# primero.net
KiCad netlist of a schematic drawn in EAGLE
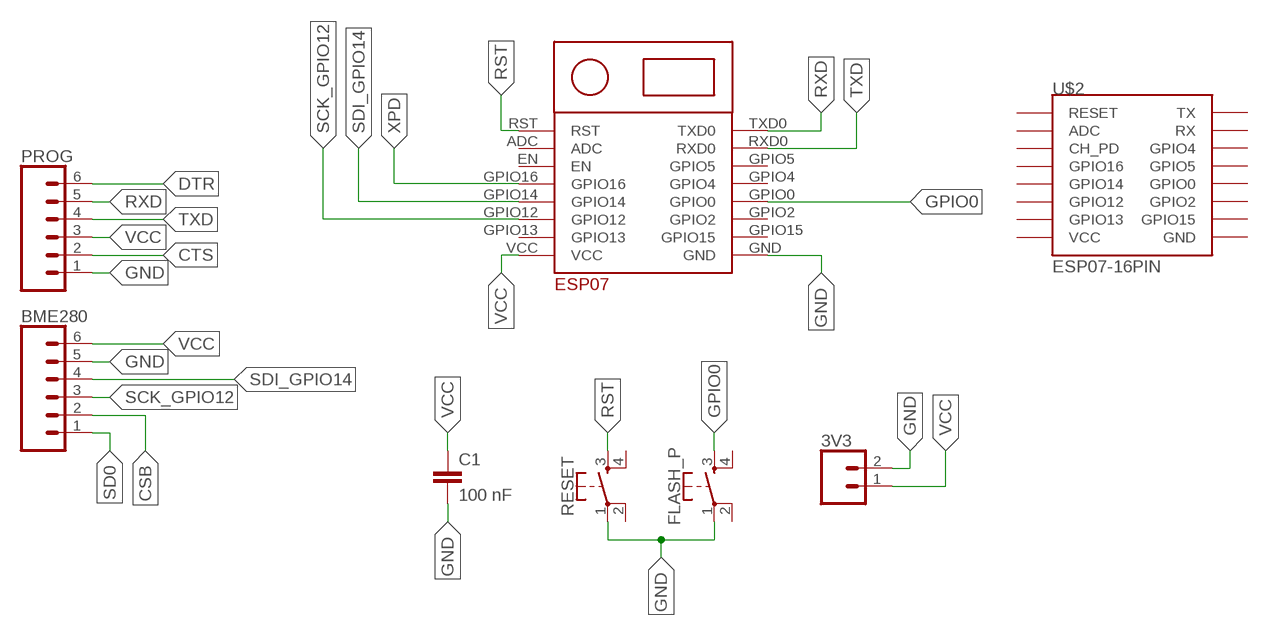
[diagram p0: schematic, sheet 1]

(export (version "E")
  (design (tool "Eeschema 10.0.6"))
  (components
    (comp (ref "3V3")
      (value "CONN_02JST-PTH-2")
      (footprint "eagle-import:JST-2-PTH")
      (libsource (lib "eagle-import") (part "CONN_02JST-PTH-2"))
    )
    (comp (ref "BME280")
      (value "CONN_06SILK_FEMALE_PTH")
      (footprint "eagle-import:1X06")
      (libsource (lib "eagle-import") (part "CONN_06SILK_FEMALE_PTH"))
    )
    (comp (ref "C1")
      (value "100 nF")
      (footprint "eagle-import:C0805")
      (libsource (lib "eagle-import") (part "C-EUC0805"))
    )
    (comp (ref "FLASH_P")
      (value "MOMENTARY-SWITCH-SPST-2-SMD-4.6X2.8MM")
      (footprint "eagle-import:TACTILE_SWITCH_SMD_4.6X2.8MM")
      (libsource (lib "eagle-import") (part "MOMENTARY-SWITCH-SPST-2-SMD-4.6X2.8MM"))
    )
    (comp (ref "PROG")
      (value "CONN_06SILK_FEMALE_PTH")
      (footprint "eagle-import:1X06")
      (libsource (lib "eagle-import") (part "CONN_06SILK_FEMALE_PTH"))
    )
    (comp (ref "RESET")
      (value "MOMENTARY-SWITCH-SPST-2-SMD-4.6X2.8MM")
      (footprint "eagle-import:TACTILE_SWITCH_SMD_4.6X2.8MM")
      (libsource (lib "eagle-import") (part "MOMENTARY-SWITCH-SPST-2-SMD-4.6X2.8MM"))
    )
    (comp (ref "U$1")
      (value "ESP-07ESP07")
      (footprint "eagle-import:ESP-07_MM")
      (libsource (lib "eagle-import") (part "ESP-07ESP07"))
    )
    (comp (ref "U$2")
      (value "ESP07-16PIN")
      (footprint "eagle-import:ESP07-16PIN")
      (libsource (lib "eagle-import") (part "ESP07-16PIN"))
    )
  )
  (nets
    (net (code "1") (name "CSB") (class "Default")
      (node (ref "BME280") (pin "2") (pinfunction "2_2") (pintype "passive"))
    )
    (net (code "2") (name "CTS") (class "Default")
      (node (ref "PROG") (pin "2") (pinfunction "2_2") (pintype "passive"))
    )
    (net (code "3") (name "DTR") (class "Default")
      (node (ref "PROG") (pin "6") (pinfunction "6_6") (pintype "passive"))
    )
    (net (code "4") (name "GND") (class "Default")
      (node (ref "3V3") (pin "2") (pinfunction "2_2") (pintype "passive"))
      (node (ref "BME280") (pin "5") (pinfunction "5_5") (pintype "passive"))
      (node (ref "C1") (pin "2") (pinfunction "2_2") (pintype "passive"))
      (node (ref "FLASH_P") (pin "1") (pinfunction "1_1") (pintype "passive"))
      (node (ref "PROG") (pin "1") (pinfunction "1_1") (pintype "passive"))
      (node (ref "RESET") (pin "1") (pinfunction "1_1") (pintype "passive"))
      (node (ref "U$1") (pin "GND") (pinfunction "GND_GND") (pintype "bidirectional"))
    )
    (net (code "5") (name "GPIO0") (class "Default")
      (node (ref "FLASH_P") (pin "3") (pinfunction "3_3") (pintype "passive"))
      (node (ref "U$1") (pin "GPIO0") (pinfunction "GPIO0_GPIO0") (pintype "bidirectional"))
    )
    (net (code "6") (name "RST") (class "Default")
      (node (ref "RESET") (pin "3") (pinfunction "3_3") (pintype "passive"))
      (node (ref "U$1") (pin "RST") (pinfunction "RST_RST") (pintype "bidirectional"))
    )
    (net (code "7") (name "RXD") (class "Default")
      (node (ref "PROG") (pin "5") (pinfunction "5_5") (pintype "passive"))
      (node (ref "U$1") (pin "TXD0") (pinfunction "TXD0_TXD0") (pintype "bidirectional"))
    )
    (net (code "8") (name "SCK_GPIO12") (class "Default")
      (node (ref "BME280") (pin "3") (pinfunction "3_3") (pintype "passive"))
      (node (ref "U$1") (pin "GPIO12") (pinfunction "GPIO12_GPIO12") (pintype "bidirectional"))
    )
    (net (code "9") (name "SD0") (class "Default")
      (node (ref "BME280") (pin "1") (pinfunction "1_1") (pintype "passive"))
    )
    (net (code "10") (name "SDI_GPIO14") (class "Default")
      (node (ref "BME280") (pin "4") (pinfunction "4_4") (pintype "passive"))
      (node (ref "U$1") (pin "GPIO14") (pinfunction "GPIO14_GPIO14") (pintype "bidirectional"))
    )
    (net (code "11") (name "TXD") (class "Default")
      (node (ref "PROG") (pin "4") (pinfunction "4_4") (pintype "passive"))
      (node (ref "U$1") (pin "RXD0") (pinfunction "RXD0_RXD0") (pintype "bidirectional"))
    )
    (net (code "12") (name "VCC") (class "Default")
      (node (ref "3V3") (pin "1") (pinfunction "1_1") (pintype "passive"))
      (node (ref "BME280") (pin "6") (pinfunction "6_6") (pintype "passive"))
      (node (ref "C1") (pin "1") (pinfunction "1_1") (pintype "passive"))
      (node (ref "PROG") (pin "3") (pinfunction "3_3") (pintype "passive"))
      (node (ref "U$1") (pin "VCC") (pinfunction "VCC_VCC") (pintype "bidirectional"))
    )
    (net (code "13") (name "XPD") (class "Default")
      (node (ref "U$1") (pin "GPIO16") (pinfunction "GPIO16_GPIO16") (pintype "bidirectional"))
    )
    (net (code "14") (name "unconnected-(FLASH_P-Pad2)") (class "Default")
      (node (ref "FLASH_P") (pin "2") (pinfunction "2_2") (pintype "passive"))
    )
    (net (code "15") (name "unconnected-(FLASH_P-Pad4)") (class "Default")
      (node (ref "FLASH_P") (pin "4") (pinfunction "4_4") (pintype "passive"))
    )
    (net (code "16") (name "unconnected-(RESET-Pad2)") (class "Default")
      (node (ref "RESET") (pin "2") (pinfunction "2_2") (pintype "passive"))
    )
    (net (code "17") (name "unconnected-(RESET-Pad4)") (class "Default")
      (node (ref "RESET") (pin "4") (pinfunction "4_4") (pintype "passive"))
    )
    (net (code "18") (name "unconnected-(U$1-PadADC)") (class "Default")
      (node (ref "U$1") (pin "ADC") (pinfunction "ADC_ADC") (pintype "bidirectional"))
    )
    (net (code "19") (name "unconnected-(U$1-PadEN)") (class "Default")
      (node (ref "U$1") (pin "EN") (pinfunction "EN_EN") (pintype "bidirectional"))
    )
    (net (code "20") (name "unconnected-(U$1-PadGPIO2)") (class "Default")
      (node (ref "U$1") (pin "GPIO2") (pinfunction "GPIO2_GPIO2") (pintype "bidirectional"))
    )
    (net (code "21") (name "unconnected-(U$1-PadGPIO4)") (class "Default")
      (node (ref "U$1") (pin "GPIO4") (pinfunction "GPIO4_GPIO4") (pintype "bidirectional"))
    )
    (net (code "22") (name "unconnected-(U$1-PadGPIO5)") (class "Default")
      (node (ref "U$1") (pin "GPIO5") (pinfunction "GPIO5_GPIO5") (pintype "bidirectional"))
    )
    (net (code "23") (name "unconnected-(U$1-PadGPIO13)") (class "Default")
      (node (ref "U$1") (pin "GPIO13") (pinfunction "GPIO13_GPIO13") (pintype "bidirectional"))
    )
    (net (code "24") (name "unconnected-(U$1-PadGPIO15)") (class "Default")
      (node (ref "U$1") (pin "GPIO15") (pinfunction "GPIO15_GPIO15") (pintype "bidirectional"))
    )
    (net (code "25") (name "unconnected-(U$2-PadADC)") (class "Default")
      (node (ref "U$2") (pin "ADC") (pinfunction "ADC_ADC") (pintype "bidirectional"))
    )
    (net (code "26") (name "unconnected-(U$2-PadCH_PD)") (class "Default")
      (node (ref "U$2") (pin "CH_PD") (pinfunction "CH_PD_CH_PD") (pintype "bidirectional"))
    )
    (net (code "27") (name "unconnected-(U$2-PadGND)") (class "Default")
      (node (ref "U$2") (pin "GND") (pinfunction "GND_GND") (pintype "bidirectional"))
    )
    (net (code "28") (name "unconnected-(U$2-PadGPIO0)") (class "Default")
      (node (ref "U$2") (pin "GPIO0") (pinfunction "GPIO0_GPIO0") (pintype "bidirectional"))
    )
    (net (code "29") (name "unconnected-(U$2-PadGPIO2)") (class "Default")
      (node (ref "U$2") (pin "GPIO2") (pinfunction "GPIO2_GPIO2") (pintype "bidirectional"))
    )
    (net (code "30") (name "unconnected-(U$2-PadGPIO4)") (class "Default")
      (node (ref "U$2") (pin "GPIO4") (pinfunction "GPIO4_GPIO4") (pintype "bidirectional"))
    )
    (net (code "31") (name "unconnected-(U$2-PadGPIO5)") (class "Default")
      (node (ref "U$2") (pin "GPIO5") (pinfunction "GPIO5_GPIO5") (pintype "bidirectional"))
    )
    (net (code "32") (name "unconnected-(U$2-PadGPIO12)") (class "Default")
      (node (ref "U$2") (pin "GPIO12") (pinfunction "GPIO12_GPIO12") (pintype "bidirectional"))
    )
    (net (code "33") (name "unconnected-(U$2-PadGPIO13)") (class "Default")
      (node (ref "U$2") (pin "GPIO13") (pinfunction "GPIO13_GPIO13") (pintype "bidirectional"))
    )
    (net (code "34") (name "unconnected-(U$2-PadGPIO14)") (class "Default")
      (node (ref "U$2") (pin "GPIO14") (pinfunction "GPIO14_GPIO14") (pintype "bidirectional"))
    )
    (net (code "35") (name "unconnected-(U$2-PadGPIO15)") (class "Default")
      (node (ref "U$2") (pin "GPIO15") (pinfunction "GPIO15_GPIO15") (pintype "bidirectional"))
    )
    (net (code "36") (name "unconnected-(U$2-PadGPIO16)") (class "Default")
      (node (ref "U$2") (pin "GPIO16") (pinfunction "GPIO16_GPIO16") (pintype "bidirectional"))
    )
    (net (code "37") (name "unconnected-(U$2-PadRX)") (class "Default")
      (node (ref "U$2") (pin "RX") (pinfunction "RX_RX") (pintype "bidirectional"))
    )
    (net (code "38") (name "unconnected-(U$2-PadTX)") (class "Default")
      (node (ref "U$2") (pin "TX") (pinfunction "TX_TX") (pintype "bidirectional"))
    )
    (net (code "39") (name "unconnected-(U$2-PadVCC)") (class "Default")
      (node (ref "U$2") (pin "VCC") (pinfunction "VCC_VCC") (pintype "bidirectional"))
    )
    (net (code "40") (name "unconnected-(U$2-RESET-PadREST)") (class "Default")
      (node (ref "U$2") (pin "REST") (pinfunction "RESET_REST") (pintype "bidirectional"))
    )
  )
)
